# ospy_hw3_3.net
KiCad netlist of a schematic drawn in EAGLE
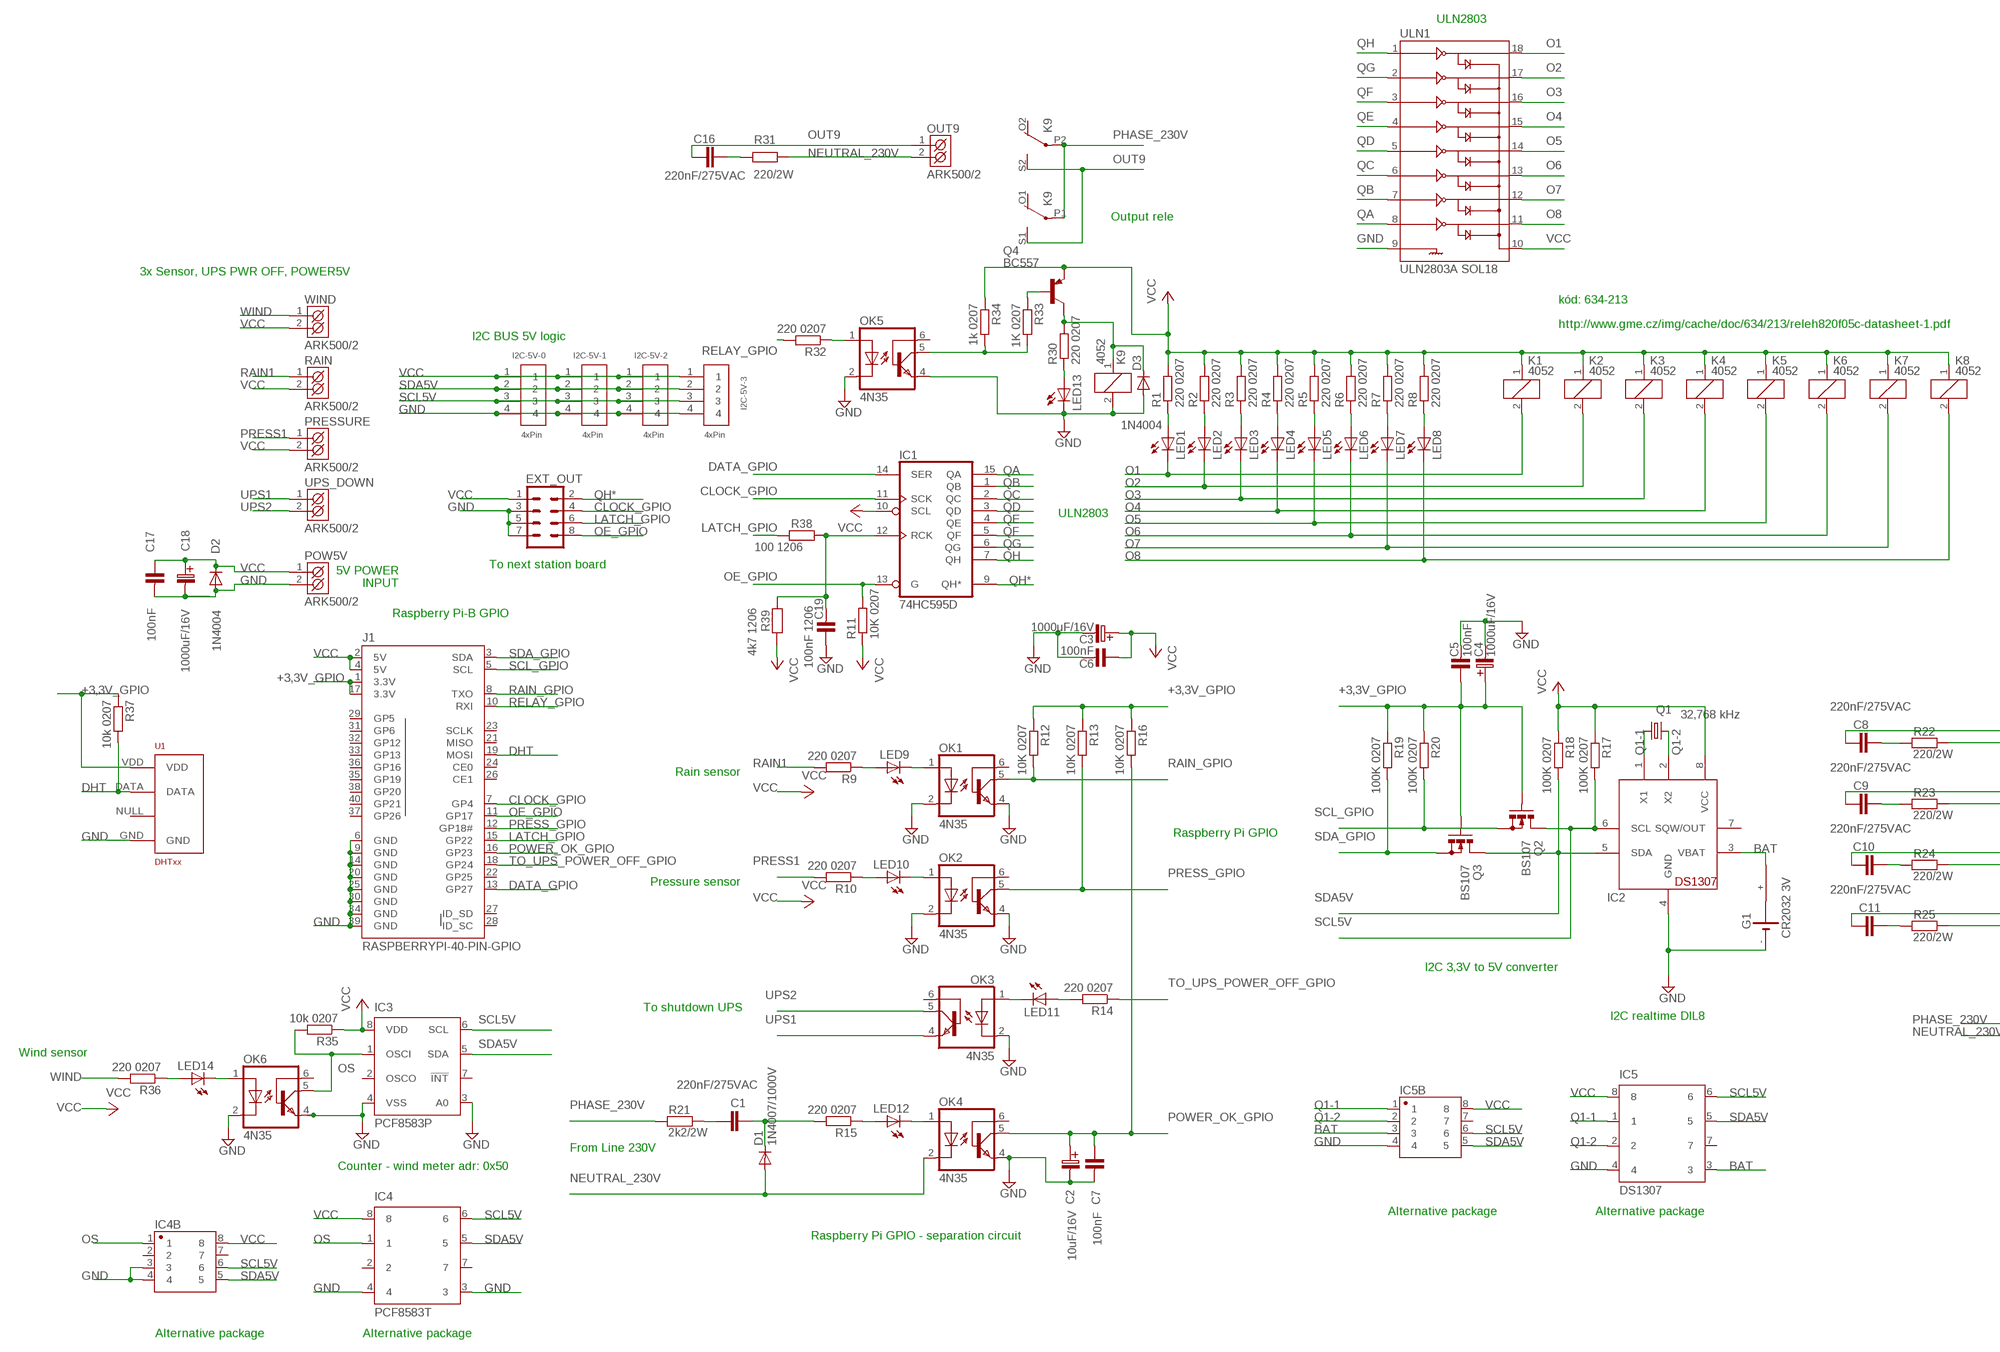
[diagram p0: schematic, sheet 1, part 1 of 2]
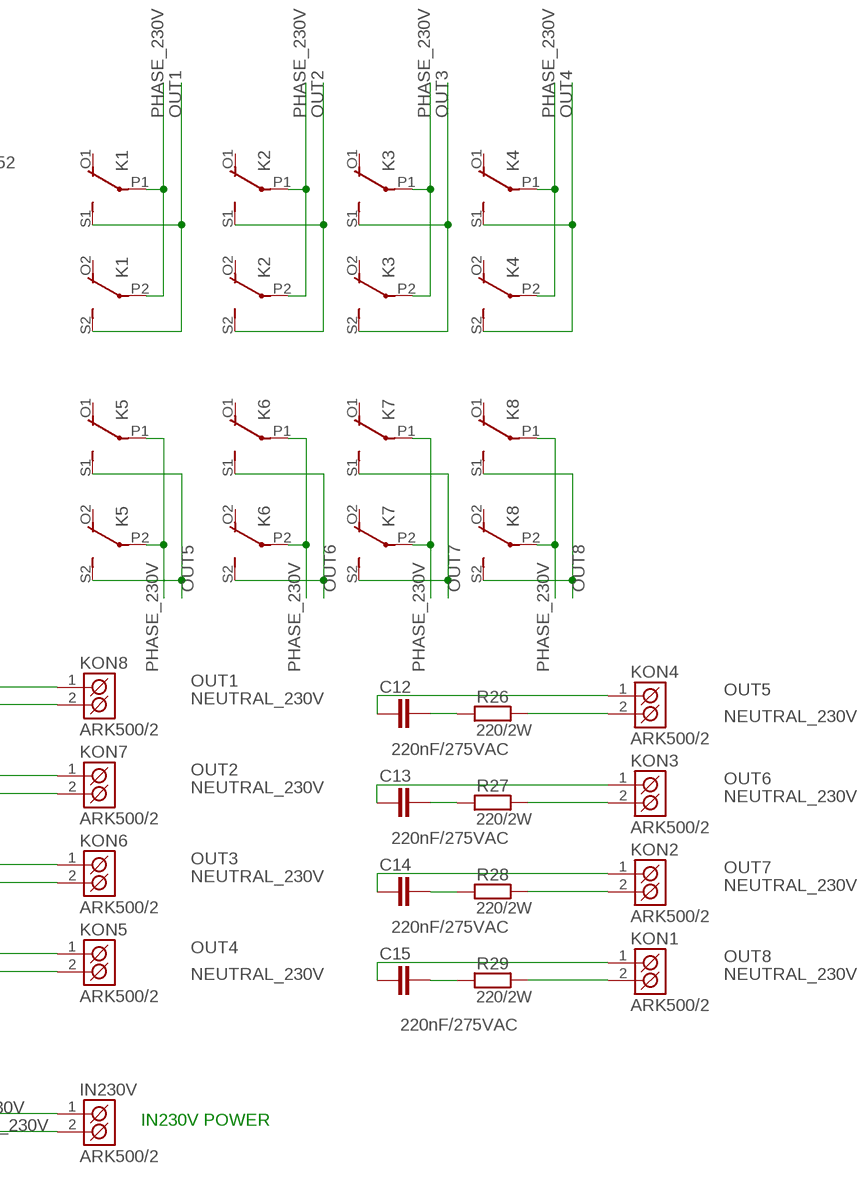
[diagram p1: schematic, sheet 1, part 2 of 2]

(export (version "E")
  (design (tool "Eeschema 10.0.6"))
  (components
    (comp (ref "C1")
      (value "220nF/275VAC")
      (footprint "eagle-import:C225-087X268")
      (libsource (lib "eagle-import") (part "C-EU225-087X268"))
    )
    (comp (ref "C2")
      (value "10uF/16V")
      (footprint "eagle-import:C_EL_5")
      (libsource (lib "eagle-import") (part "#_RADIAL_POUZDRA5"))
    )
    (comp (ref "C3")
      (value "1000uF/16V")
      (footprint "eagle-import:C_EL_5")
      (libsource (lib "eagle-import") (part "#_RADIAL_POUZDRA5"))
    )
    (comp (ref "C4")
      (value "1000uF/16V")
      (footprint "eagle-import:C_EL_5")
      (libsource (lib "eagle-import") (part "#_RADIAL_POUZDRA5"))
    )
    (comp (ref "C5")
      (value "100nF")
      (footprint "eagle-import:RM5_2,5")
      (libsource (lib "eagle-import") (part "100N-J/63V"))
    )
    (comp (ref "C6")
      (value "100nF")
      (footprint "eagle-import:RM5_2,5")
      (libsource (lib "eagle-import") (part "100N-J/63V"))
    )
    (comp (ref "C7")
      (value "100nF")
      (footprint "eagle-import:RM5_2,5")
      (libsource (lib "eagle-import") (part "100N-J/63V"))
    )
    (comp (ref "C8")
      (value "220nF/275VAC")
      (footprint "eagle-import:C225-087X268")
      (libsource (lib "eagle-import") (part "C-EU225-087X268"))
    )
    (comp (ref "C9")
      (value "220nF/275VAC")
      (footprint "eagle-import:C225-087X268")
      (libsource (lib "eagle-import") (part "C-EU225-087X268"))
    )
    (comp (ref "C10")
      (value "220nF/275VAC")
      (footprint "eagle-import:C225-087X268")
      (libsource (lib "eagle-import") (part "C-EU225-087X268"))
    )
    (comp (ref "C11")
      (value "220nF/275VAC")
      (footprint "eagle-import:C225-087X268")
      (libsource (lib "eagle-import") (part "C-EU225-087X268"))
    )
    (comp (ref "C12")
      (value "220nF/275VAC")
      (footprint "eagle-import:C225-087X268")
      (libsource (lib "eagle-import") (part "C-EU225-087X268"))
    )
    (comp (ref "C13")
      (value "220nF/275VAC")
      (footprint "eagle-import:C225-087X268")
      (libsource (lib "eagle-import") (part "C-EU225-087X268"))
    )
    (comp (ref "C14")
      (value "220nF/275VAC")
      (footprint "eagle-import:C225-087X268")
      (libsource (lib "eagle-import") (part "C-EU225-087X268"))
    )
    (comp (ref "C15")
      (value "220nF/275VAC")
      (footprint "eagle-import:C225-087X268")
      (libsource (lib "eagle-import") (part "C-EU225-087X268"))
    )
    (comp (ref "C16")
      (value "220nF/275VAC")
      (footprint "eagle-import:C225-087X268")
      (libsource (lib "eagle-import") (part "C-EU225-087X268"))
    )
    (comp (ref "C17")
      (value "100nF")
      (footprint "eagle-import:RM5_2,5")
      (libsource (lib "eagle-import") (part "100N-J/63V"))
    )
    (comp (ref "C18")
      (value "1000uF/16V")
      (footprint "eagle-import:C_EL_5")
      (libsource (lib "eagle-import") (part "#_RADIAL_POUZDRA5"))
    )
    (comp (ref "C19")
      (value "100nF 1206")
      (footprint "eagle-import:1206")
      (libsource (lib "eagle-import") (part "C-KER_1206"))
    )
    (comp (ref "D1")
      (value "1N4007/1000V")
      (footprint "eagle-import:DO41-10")
      (libsource (lib "eagle-import") (part "diode_1N4004"))
    )
    (comp (ref "D2")
      (value "1N4004")
      (footprint "eagle-import:DO41-10")
      (libsource (lib "eagle-import") (part "1N4004"))
    )
    (comp (ref "D3")
      (value "1N4004")
      (footprint "eagle-import:DO41-10")
      (libsource (lib "eagle-import") (part "1N4004"))
    )
    (comp (ref "EXT_OUT")
      (value "M04X2")
      (footprint "eagle-import:2X4")
      (libsource (lib "eagle-import") (part "M04X2"))
    )
    (comp (ref "G1")
      (value "CR2032 3V")
      (footprint "eagle-import:B2430UNI")
      (libsource (lib "eagle-import") (part "B2430UNI"))
    )
    (comp (ref "I2C-5V-0")
      (value "4xPin")
      (footprint "eagle-import:1X04-CLEANBIG")
      (libsource (lib "eagle-import") (part "1X4-CLEANBIG"))
    )
    (comp (ref "I2C-5V-1")
      (value "4xPin")
      (footprint "eagle-import:1X04-CLEANBIG")
      (libsource (lib "eagle-import") (part "1X4-CLEANBIG"))
    )
    (comp (ref "I2C-5V-2")
      (value "4xPin")
      (footprint "eagle-import:1X04-CLEANBIG")
      (libsource (lib "eagle-import") (part "1X4-CLEANBIG"))
    )
    (comp (ref "I2C-5V-3")
      (value "4xPin")
      (footprint "eagle-import:1X04-CLEANBIG")
      (libsource (lib "eagle-import") (part "1X4-CLEANBIG"))
    )
    (comp (ref "IC1")
      (value "74HC595D")
      (footprint "eagle-import:SO16")
      (libsource (lib "eagle-import") (part "74595DHC"))
    )
    (comp (ref "IC2")
      (value "DS1307")
      (footprint "eagle-import:DIL08")
      (libsource (lib "eagle-import") (part "DS1307"))
    )
    (comp (ref "IC3")
      (value "PCF8583P")
      (footprint "eagle-import:DIL08")
      (libsource (lib "eagle-import") (part "ds1307_pcf8583_PCF8583P"))
    )
    (comp (ref "IC4")
      (value "PCF8583T")
      (footprint "eagle-import:SO8-7_5")
      (libsource (lib "eagle-import") (part "PCF8583T"))
    )
    (comp (ref "IC4B")
      (value "GENERIC-SOIC8")
      (footprint "eagle-import:SO08-UNIVERSAL")
      (libsource (lib "eagle-import") (part "GENERIC-SOIC8"))
    )
    (comp (ref "IC5")
      (value "DS1307")
      (footprint "eagle-import:SO8-7_5")
      (libsource (lib "eagle-import") (part "PCF8583T"))
    )
    (comp (ref "IC5B")
      (value "GENERIC-SOIC8")
      (footprint "eagle-import:SO08-UNIVERSAL")
      (libsource (lib "eagle-import") (part "GENERIC-SOIC8"))
    )
    (comp (ref "IN230V")
      (value "ARK500/2")
      (footprint "eagle-import:ARK500_2")
      (libsource (lib "eagle-import") (part "ARK500/2"))
    )
    (comp (ref "J1")
      (value "RASPBERRYPI-40-PIN-GPIO")
      (footprint "eagle-import:2X20-SHROUDED")
      (libsource (lib "eagle-import") (part "RASPBERRYPI-40-PIN-GPIO"))
    )
    (comp (ref "K1")
      (value "4052")
      (footprint "eagle-import:F4052")
      (libsource (lib "eagle-import") (part "4052"))
    )
    (comp (ref "K2")
      (value "4052")
      (footprint "eagle-import:F4052")
      (libsource (lib "eagle-import") (part "4052"))
    )
    (comp (ref "K3")
      (value "4052")
      (footprint "eagle-import:F4052")
      (libsource (lib "eagle-import") (part "4052"))
    )
    (comp (ref "K4")
      (value "4052")
      (footprint "eagle-import:F4052")
      (libsource (lib "eagle-import") (part "4052"))
    )
    (comp (ref "K5")
      (value "4052")
      (footprint "eagle-import:F4052")
      (libsource (lib "eagle-import") (part "4052"))
    )
    (comp (ref "K6")
      (value "4052")
      (footprint "eagle-import:F4052")
      (libsource (lib "eagle-import") (part "4052"))
    )
    (comp (ref "K7")
      (value "4052")
      (footprint "eagle-import:F4052")
      (libsource (lib "eagle-import") (part "4052"))
    )
    (comp (ref "K8")
      (value "4052")
      (footprint "eagle-import:F4052")
      (libsource (lib "eagle-import") (part "4052"))
    )
    (comp (ref "K9")
      (value "4052")
      (footprint "eagle-import:F4052")
      (libsource (lib "eagle-import") (part "4052"))
    )
    (comp (ref "KON1")
      (value "ARK500/2")
      (footprint "eagle-import:ARK500_2")
      (libsource (lib "eagle-import") (part "ARK500/2"))
    )
    (comp (ref "KON2")
      (value "ARK500/2")
      (footprint "eagle-import:ARK500_2")
      (libsource (lib "eagle-import") (part "ARK500/2"))
    )
    (comp (ref "KON3")
      (value "ARK500/2")
      (footprint "eagle-import:ARK500_2")
      (libsource (lib "eagle-import") (part "ARK500/2"))
    )
    (comp (ref "KON4")
      (value "ARK500/2")
      (footprint "eagle-import:ARK500_2")
      (libsource (lib "eagle-import") (part "ARK500/2"))
    )
    (comp (ref "KON5")
      (value "ARK500/2")
      (footprint "eagle-import:ARK500_2")
      (libsource (lib "eagle-import") (part "ARK500/2"))
    )
    (comp (ref "KON6")
      (value "ARK500/2")
      (footprint "eagle-import:ARK500_2")
      (libsource (lib "eagle-import") (part "ARK500/2"))
    )
    (comp (ref "KON7")
      (value "ARK500/2")
      (footprint "eagle-import:ARK500_2")
      (libsource (lib "eagle-import") (part "ARK500/2"))
    )
    (comp (ref "KON8")
      (value "ARK500/2")
      (footprint "eagle-import:ARK500_2")
      (libsource (lib "eagle-import") (part "ARK500/2"))
    )
    (comp (ref "LED1")
      (value "LED3MM")
      (footprint "eagle-import:LED3MM")
      (libsource (lib "eagle-import") (part "LED3MM"))
    )
    (comp (ref "LED2")
      (value "LED3MM")
      (footprint "eagle-import:LED3MM")
      (libsource (lib "eagle-import") (part "LED3MM"))
    )
    (comp (ref "LED3")
      (value "LED3MM")
      (footprint "eagle-import:LED3MM")
      (libsource (lib "eagle-import") (part "LED3MM"))
    )
    (comp (ref "LED4")
      (value "LED3MM")
      (footprint "eagle-import:LED3MM")
      (libsource (lib "eagle-import") (part "LED3MM"))
    )
    (comp (ref "LED5")
      (value "LED3MM")
      (footprint "eagle-import:LED3MM")
      (libsource (lib "eagle-import") (part "LED3MM"))
    )
    (comp (ref "LED6")
      (value "LED3MM")
      (footprint "eagle-import:LED3MM")
      (libsource (lib "eagle-import") (part "LED3MM"))
    )
    (comp (ref "LED7")
      (value "LED3MM")
      (footprint "eagle-import:LED3MM")
      (libsource (lib "eagle-import") (part "LED3MM"))
    )
    (comp (ref "LED8")
      (value "LED3MM")
      (footprint "eagle-import:LED3MM")
      (libsource (lib "eagle-import") (part "LED3MM"))
    )
    (comp (ref "LED9")
      (value "LED3MM")
      (footprint "eagle-import:LED3MM")
      (libsource (lib "eagle-import") (part "LED3MM"))
    )
    (comp (ref "LED10")
      (value "LED3MM")
      (footprint "eagle-import:LED3MM")
      (libsource (lib "eagle-import") (part "LED3MM"))
    )
    (comp (ref "LED11")
      (value "LED3MM")
      (footprint "eagle-import:LED3MM")
      (libsource (lib "eagle-import") (part "LED3MM"))
    )
    (comp (ref "LED12")
      (value "LED3MM")
      (footprint "eagle-import:LED3MM")
      (libsource (lib "eagle-import") (part "LED3MM"))
    )
    (comp (ref "LED13")
      (value "LED3MM")
      (footprint "eagle-import:LED3MM")
      (libsource (lib "eagle-import") (part "LED3MM"))
    )
    (comp (ref "LED14")
      (value "LED3MM")
      (footprint "eagle-import:LED3MM")
      (libsource (lib "eagle-import") (part "LED3MM"))
    )
    (comp (ref "OK1")
      (value "4N35")
      (footprint "eagle-import:DIL06")
      (fields (field (name "MF") "FAIRCHILD SEMICONDUCTOR"))
      (libsource (lib "eagle-import") (part "4N35"))
    )
    (comp (ref "OK2")
      (value "4N35")
      (footprint "eagle-import:DIL06")
      (fields (field (name "MF") "FAIRCHILD SEMICONDUCTOR"))
      (libsource (lib "eagle-import") (part "4N35"))
    )
    (comp (ref "OK3")
      (value "4N35")
      (footprint "eagle-import:DIL06")
      (fields (field (name "MF") "FAIRCHILD SEMICONDUCTOR"))
      (libsource (lib "eagle-import") (part "4N35"))
    )
    (comp (ref "OK4")
      (value "4N35")
      (footprint "eagle-import:DIL06")
      (fields (field (name "MF") "FAIRCHILD SEMICONDUCTOR"))
      (libsource (lib "eagle-import") (part "4N35"))
    )
    (comp (ref "OK5")
      (value "4N35")
      (footprint "eagle-import:DIL06")
      (fields (field (name "MF") "FAIRCHILD SEMICONDUCTOR"))
      (libsource (lib "eagle-import") (part "4N35"))
    )
    (comp (ref "OK6")
      (value "4N35")
      (footprint "eagle-import:DIL06")
      (fields (field (name "MF") "FAIRCHILD SEMICONDUCTOR"))
      (libsource (lib "eagle-import") (part "4N35"))
    )
    (comp (ref "OUT9")
      (value "ARK500/2")
      (footprint "eagle-import:ARK500_2")
      (libsource (lib "eagle-import") (part "ARK500/2"))
    )
    (comp (ref "POW5V")
      (value "ARK500/2")
      (footprint "eagle-import:ARK500_2")
      (libsource (lib "eagle-import") (part "ARK500/2"))
    )
    (comp (ref "PRESSURE")
      (value "ARK500/2")
      (footprint "eagle-import:ARK500_2")
      (libsource (lib "eagle-import") (part "ARK500/2"))
    )
    (comp (ref "Q1")
      (value "32,768 kHz")
      (footprint "eagle-import:TC26V")
      (libsource (lib "eagle-import") (part "CRYSTALTC26V"))
    )
    (comp (ref "Q2")
      (value "BS107")
      (footprint "eagle-import:SOT54E")
      (libsource (lib "eagle-import") (part "BS170"))
    )
    (comp (ref "Q3")
      (value "BS107")
      (footprint "eagle-import:SOT54E")
      (libsource (lib "eagle-import") (part "BS170"))
    )
    (comp (ref "Q4")
      (value "BC557")
      (footprint "eagle-import:TO92")
      (libsource (lib "eagle-import") (part "BC557"))
    )
    (comp (ref "R1")
      (value "220 0207")
      (footprint "eagle-import:0207_10")
      (libsource (lib "eagle-import") (part "R-EU_0207/10"))
    )
    (comp (ref "R2")
      (value "220 0207")
      (footprint "eagle-import:0207_10")
      (libsource (lib "eagle-import") (part "R-EU_0207/10"))
    )
    (comp (ref "R3")
      (value "220 0207")
      (footprint "eagle-import:0207_10")
      (libsource (lib "eagle-import") (part "R-EU_0207/10"))
    )
    (comp (ref "R4")
      (value "220 0207")
      (footprint "eagle-import:0207_10")
      (libsource (lib "eagle-import") (part "R-EU_0207/10"))
    )
    (comp (ref "R5")
      (value "220 0207")
      (footprint "eagle-import:0207_10")
      (libsource (lib "eagle-import") (part "R-EU_0207/10"))
    )
    (comp (ref "R6")
      (value "220 0207")
      (footprint "eagle-import:0207_10")
      (libsource (lib "eagle-import") (part "R-EU_0207/10"))
    )
    (comp (ref "R7")
      (value "220 0207")
      (footprint "eagle-import:0207_10")
      (libsource (lib "eagle-import") (part "R-EU_0207/10"))
    )
    (comp (ref "R8")
      (value "220 0207")
      (footprint "eagle-import:0207_10")
      (libsource (lib "eagle-import") (part "R-EU_0207/10"))
    )
    (comp (ref "R9")
      (value "220 0207")
      (footprint "eagle-import:0207_10")
      (libsource (lib "eagle-import") (part "R-EU_0207/10"))
    )
    (comp (ref "R10")
      (value "220 0207")
      (footprint "eagle-import:0207_10")
      (libsource (lib "eagle-import") (part "R-EU_0207/10"))
    )
    (comp (ref "R11")
      (value "10K 0207")
      (footprint "eagle-import:0207_10")
      (libsource (lib "eagle-import") (part "R-EU_0207/10"))
    )
    (comp (ref "R12")
      (value "10K 0207")
      (footprint "eagle-import:0207_10")
      (libsource (lib "eagle-import") (part "R-EU_0207/10"))
    )
    (comp (ref "R13")
      (value "10K 0207")
      (footprint "eagle-import:0207_10")
      (libsource (lib "eagle-import") (part "R-EU_0207/10"))
    )
    (comp (ref "R14")
      (value "220 0207")
      (footprint "eagle-import:0207_10")
      (libsource (lib "eagle-import") (part "R-EU_0207/10"))
    )
    (comp (ref "R15")
      (value "220 0207")
      (footprint "eagle-import:0207_10")
      (libsource (lib "eagle-import") (part "R-EU_0207/10"))
    )
    (comp (ref "R16")
      (value "10K 0207")
      (footprint "eagle-import:0207_10")
      (libsource (lib "eagle-import") (part "R-EU_0207/10"))
    )
    (comp (ref "R17")
      (value "100K 0207")
      (footprint "eagle-import:0207_10")
      (libsource (lib "eagle-import") (part "R-EU_0207/10"))
    )
    (comp (ref "R18")
      (value "100K 0207")
      (footprint "eagle-import:0207_10")
      (libsource (lib "eagle-import") (part "R-EU_0207/10"))
    )
    (comp (ref "R19")
      (value "100K 0207")
      (footprint "eagle-import:0207_10")
      (libsource (lib "eagle-import") (part "R-EU_0207/10"))
    )
    (comp (ref "R20")
      (value "100K 0207")
      (footprint "eagle-import:0207_10")
      (libsource (lib "eagle-import") (part "R-EU_0207/10"))
    )
    (comp (ref "R21")
      (value "2k2/2W")
      (footprint "eagle-import:R__2W")
      (libsource (lib "eagle-import") (part "W2_220R"))
    )
    (comp (ref "R22")
      (value "220/2W")
      (footprint "eagle-import:R__2W")
      (libsource (lib "eagle-import") (part "W2_220R"))
    )
    (comp (ref "R23")
      (value "220/2W")
      (footprint "eagle-import:R__2W")
      (libsource (lib "eagle-import") (part "W2_220R"))
    )
    (comp (ref "R24")
      (value "220/2W")
      (footprint "eagle-import:R__2W")
      (libsource (lib "eagle-import") (part "W2_220R"))
    )
    (comp (ref "R25")
      (value "220/2W")
      (footprint "eagle-import:R__2W")
      (libsource (lib "eagle-import") (part "W2_220R"))
    )
    (comp (ref "R26")
      (value "220/2W")
      (footprint "eagle-import:R__2W")
      (libsource (lib "eagle-import") (part "W2_220R"))
    )
    (comp (ref "R27")
      (value "220/2W")
      (footprint "eagle-import:R__2W")
      (libsource (lib "eagle-import") (part "W2_220R"))
    )
    (comp (ref "R28")
      (value "220/2W")
      (footprint "eagle-import:R__2W")
      (libsource (lib "eagle-import") (part "W2_220R"))
    )
    (comp (ref "R29")
      (value "220/2W")
      (footprint "eagle-import:R__2W")
      (libsource (lib "eagle-import") (part "W2_220R"))
    )
    (comp (ref "R30")
      (value "220 0207")
      (footprint "eagle-import:0207_10")
      (libsource (lib "eagle-import") (part "R-EU_0207/10"))
    )
    (comp (ref "R31")
      (value "220/2W")
      (footprint "eagle-import:R__2W")
      (libsource (lib "eagle-import") (part "W2_220R"))
    )
    (comp (ref "R32")
      (value "220 0207")
      (footprint "eagle-import:0207_10")
      (libsource (lib "eagle-import") (part "R-EU_0207/10"))
    )
    (comp (ref "R33")
      (value "1K 0207")
      (footprint "eagle-import:0207_10")
      (libsource (lib "eagle-import") (part "R-EU_0207/10"))
    )
    (comp (ref "R34")
      (value "1k 0207")
      (footprint "eagle-import:0207_10")
      (libsource (lib "eagle-import") (part "R-EU_0207/10"))
    )
    (comp (ref "R35")
      (value "10k 0207")
      (footprint "eagle-import:0207_10")
      (libsource (lib "eagle-import") (part "R-EU_0207/10"))
    )
    (comp (ref "R36")
      (value "220 0207")
      (footprint "eagle-import:0207_10")
      (libsource (lib "eagle-import") (part "R-EU_0207/10"))
    )
    (comp (ref "R37")
      (value "10k 0207")
      (footprint "eagle-import:0207_10")
      (libsource (lib "eagle-import") (part "R-EU_0207/10"))
    )
    (comp (ref "R38")
      (value "100 1206")
      (footprint "eagle-import:1206")
      (libsource (lib "eagle-import") (part "R_1206"))
    )
    (comp (ref "R39")
      (value "4k7 1206")
      (footprint "eagle-import:1206")
      (libsource (lib "eagle-import") (part "R_1206"))
    )
    (comp (ref "RAIN")
      (value "ARK500/2")
      (footprint "eagle-import:ARK500_2")
      (libsource (lib "eagle-import") (part "ARK500/2"))
    )
    (comp (ref "U1")
      (value "DHTxx")
      (footprint "eagle-import:RHT03_DHT-22_RA")
      (libsource (lib "eagle-import") (part "RHT03_DHT-22_AM2302RA"))
    )
    (comp (ref "ULN1")
      (value "ULN2803A SOL18")
      (footprint "eagle-import:SO18L")
      (libsource (lib "eagle-import") (part "ULN2803SOICW"))
    )
    (comp (ref "UPS_DOWN")
      (value "ARK500/2")
      (footprint "eagle-import:ARK500_2")
      (libsource (lib "eagle-import") (part "ARK500/2"))
    )
    (comp (ref "WIND")
      (value "ARK500/2")
      (footprint "eagle-import:ARK500_2")
      (libsource (lib "eagle-import") (part "ARK500/2"))
    )
  )
  (nets
    (net (code "1") (name "/+3,3V_GPIO") (class "Default")
      (node (ref "C4") (pin "C+") (pinfunction "C_EL+_C+") (pintype "passive"))
      (node (ref "C5") (pin "1") (pinfunction "1_1") (pintype "passive"))
      (node (ref "J1") (pin "1") (pinfunction "3.3V_1") (pintype "power_in"))
      (node (ref "J1") (pin "17") (pinfunction "3.3V_17") (pintype "power_in"))
      (node (ref "Q2") (pin "G") (pinfunction "G_G") (pintype "passive"))
      (node (ref "Q3") (pin "G") (pinfunction "G_G") (pintype "passive"))
      (node (ref "R12") (pin "1") (pinfunction "1_1") (pintype "passive"))
      (node (ref "R13") (pin "1") (pinfunction "1_1") (pintype "passive"))
      (node (ref "R16") (pin "1") (pinfunction "1_1") (pintype "passive"))
      (node (ref "R19") (pin "1") (pinfunction "1_1") (pintype "passive"))
      (node (ref "R20") (pin "1") (pinfunction "1_1") (pintype "passive"))
      (node (ref "R37") (pin "1") (pinfunction "1_1") (pintype "passive"))
      (node (ref "U1") (pin "VDD") (pinfunction "VDD_VDD") (pintype "power_in"))
    )
    (net (code "2") (name "/BAT") (class "Default")
      (node (ref "G1") (pin "+") (pinfunction "+_+") (pintype "passive"))
      (node (ref "IC2") (pin "3") (pinfunction "VBAT_3") (pintype "power_in"))
      (node (ref "IC5") (pin "3") (pinfunction "3_3") (pintype "input"))
      (node (ref "IC5B") (pin "3") (pinfunction "3_3") (pintype "bidirectional"))
    )
    (net (code "3") (name "/CLOCK_GPIO") (class "Default")
      (node (ref "EXT_OUT") (pin "4") (pinfunction "4_4") (pintype "passive"))
      (node (ref "IC1") (pin "11") (pinfunction "SCK_11") (pintype "input"))
      (node (ref "J1") (pin "7") (pinfunction "GP4_7") (pintype "bidirectional"))
    )
    (net (code "4") (name "/DATA_GPIO") (class "Default")
      (node (ref "IC1") (pin "14") (pinfunction "SER_14") (pintype "input"))
      (node (ref "J1") (pin "13") (pinfunction "GP27_13") (pintype "bidirectional"))
    )
    (net (code "5") (name "/DHT") (class "Default")
      (node (ref "J1") (pin "19") (pinfunction "MOSI_19") (pintype "output"))
      (node (ref "R37") (pin "2") (pinfunction "2_2") (pintype "passive"))
      (node (ref "U1") (pin "DATA") (pinfunction "DATA_DATA") (pintype "bidirectional"))
    )
    (net (code "6") (name "/LATCH_GPIO") (class "Default")
      (node (ref "EXT_OUT") (pin "6") (pinfunction "6_6") (pintype "passive"))
      (node (ref "J1") (pin "15") (pinfunction "GP22_15") (pintype "bidirectional"))
      (node (ref "R38") (pin "1") (pinfunction "1_1") (pintype "passive"))
    )
    (net (code "7") (name "/NEUTRAL_230V") (class "Default")
      (node (ref "D1") (pin "A") (pinfunction "A_A") (pintype "passive"))
      (node (ref "IN230V") (pin "2") (pinfunction "K2_2") (pintype "passive"))
      (node (ref "KON1") (pin "2") (pinfunction "K2_2") (pintype "passive"))
      (node (ref "KON2") (pin "2") (pinfunction "K2_2") (pintype "passive"))
      (node (ref "KON3") (pin "2") (pinfunction "K2_2") (pintype "passive"))
      (node (ref "KON4") (pin "2") (pinfunction "K2_2") (pintype "passive"))
      (node (ref "KON5") (pin "2") (pinfunction "K2_2") (pintype "passive"))
      (node (ref "KON6") (pin "2") (pinfunction "K2_2") (pintype "passive"))
      (node (ref "KON7") (pin "2") (pinfunction "K2_2") (pintype "passive"))
      (node (ref "KON8") (pin "2") (pinfunction "K2_2") (pintype "passive"))
      (node (ref "OK4") (pin "2") (pinfunction "C_2") (pintype "passive"))
      (node (ref "OUT9") (pin "2") (pinfunction "K2_2") (pintype "passive"))
      (node (ref "R22") (pin "2") (pinfunction "2_2") (pintype "passive"))
      (node (ref "R23") (pin "2") (pinfunction "2_2") (pintype "passive"))
      (node (ref "R24") (pin "2") (pinfunction "2_2") (pintype "passive"))
      (node (ref "R25") (pin "2") (pinfunction "2_2") (pintype "passive"))
      (node (ref "R26") (pin "2") (pinfunction "2_2") (pintype "passive"))
      (node (ref "R27") (pin "2") (pinfunction "2_2") (pintype "passive"))
      (node (ref "R28") (pin "2") (pinfunction "2_2") (pintype "passive"))
      (node (ref "R29") (pin "2") (pinfunction "2_2") (pintype "passive"))
      (node (ref "R31") (pin "2") (pinfunction "2_2") (pintype "passive"))
    )
    (net (code "8") (name "/O1") (class "Default")
      (node (ref "K1") (pin "2") (pinfunction "2_2") (pintype "passive"))
      (node (ref "LED1") (pin "K") (pinfunction "C_K") (pintype "passive"))
      (node (ref "ULN1") (pin "18") (pinfunction "18_18") (pintype "bidirectional"))
    )
    (net (code "9") (name "/O2") (class "Default")
      (node (ref "K2") (pin "2") (pinfunction "2_2") (pintype "passive"))
      (node (ref "LED2") (pin "K") (pinfunction "C_K") (pintype "passive"))
      (node (ref "ULN1") (pin "17") (pinfunction "17_17") (pintype "bidirectional"))
    )
    (net (code "10") (name "/O3") (class "Default")
      (node (ref "K3") (pin "2") (pinfunction "2_2") (pintype "passive"))
      (node (ref "LED3") (pin "K") (pinfunction "C_K") (pintype "passive"))
      (node (ref "ULN1") (pin "16") (pinfunction "16_16") (pintype "bidirectional"))
    )
    (net (code "11") (name "/O4") (class "Default")
      (node (ref "K4") (pin "2") (pinfunction "2_2") (pintype "passive"))
      (node (ref "LED4") (pin "K") (pinfunction "C_K") (pintype "passive"))
      (node (ref "ULN1") (pin "15") (pinfunction "15_15") (pintype "bidirectional"))
    )
    (net (code "12") (name "/O5") (class "Default")
      (node (ref "K5") (pin "2") (pinfunction "2_2") (pintype "passive"))
      (node (ref "LED5") (pin "K") (pinfunction "C_K") (pintype "passive"))
      (node (ref "ULN1") (pin "14") (pinfunction "14_14") (pintype "bidirectional"))
    )
    (net (code "13") (name "/O6") (class "Default")
      (node (ref "K6") (pin "2") (pinfunction "2_2") (pintype "passive"))
      (node (ref "LED6") (pin "K") (pinfunction "C_K") (pintype "passive"))
      (node (ref "ULN1") (pin "13") (pinfunction "13_13") (pintype "bidirectional"))
    )
    (net (code "14") (name "/O7") (class "Default")
      (node (ref "K7") (pin "2") (pinfunction "2_2") (pintype "passive"))
      (node (ref "LED7") (pin "K") (pinfunction "C_K") (pintype "passive"))
      (node (ref "ULN1") (pin "12") (pinfunction "12_12") (pintype "bidirectional"))
    )
    (net (code "15") (name "/O8") (class "Default")
      (node (ref "K8") (pin "2") (pinfunction "2_2") (pintype "passive"))
      (node (ref "LED8") (pin "K") (pinfunction "C_K") (pintype "passive"))
      (node (ref "ULN1") (pin "11") (pinfunction "11_11") (pintype "bidirectional"))
    )
    (net (code "16") (name "/OE_GPIO") (class "Default")
      (node (ref "EXT_OUT") (pin "8") (pinfunction "8_8") (pintype "passive"))
      (node (ref "IC1") (pin "13") (pinfunction "G_13") (pintype "input"))
      (node (ref "J1") (pin "11") (pinfunction "GP17_11") (pintype "bidirectional"))
      (node (ref "R11") (pin "2") (pinfunction "2_2") (pintype "passive"))
    )
    (net (code "17") (name "/OS") (class "Default")
      (node (ref "IC3") (pin "1") (pinfunction "OSCI_1") (pintype "input"))
      (node (ref "IC4") (pin "1") (pinfunction "1_1") (pintype "input"))
      (node (ref "IC4B") (pin "1") (pinfunction "1_1") (pintype "bidirectional"))
      (node (ref "OK6") (pin "5") (pinfunction "COL_5") (pintype "passive"))
      (node (ref "R35") (pin "2") (pinfunction "2_2") (pintype "passive"))
    )
    (net (code "18") (name "/OUT1") (class "Default")
      (node (ref "C8") (pin "1") (pinfunction "1_1") (pintype "passive"))
      (node (ref "K1") (pin "S1") (pinfunction "S_S1") (pintype "passive"))
      (node (ref "K1") (pin "S2") (pinfunction "S_S2") (pintype "passive"))
      (node (ref "KON8") (pin "1") (pinfunction "K1_1") (pintype "passive"))
    )
    (net (code "19") (name "/OUT2") (class "Default")
      (node (ref "C9") (pin "1") (pinfunction "1_1") (pintype "passive"))
      (node (ref "K2") (pin "S1") (pinfunction "S_S1") (pintype "passive"))
      (node (ref "K2") (pin "S2") (pinfunction "S_S2") (pintype "passive"))
      (node (ref "KON7") (pin "1") (pinfunction "K1_1") (pintype "passive"))
    )
    (net (code "20") (name "/OUT3") (class "Default")
      (node (ref "C10") (pin "1") (pinfunction "1_1") (pintype "passive"))
      (node (ref "K3") (pin "S1") (pinfunction "S_S1") (pintype "passive"))
      (node (ref "K3") (pin "S2") (pinfunction "S_S2") (pintype "passive"))
      (node (ref "KON6") (pin "1") (pinfunction "K1_1") (pintype "passive"))
    )
    (net (code "21") (name "/OUT4") (class "Default")
      (node (ref "C11") (pin "1") (pinfunction "1_1") (pintype "passive"))
      (node (ref "K4") (pin "S1") (pinfunction "S_S1") (pintype "passive"))
      (node (ref "K4") (pin "S2") (pinfunction "S_S2") (pintype "passive"))
      (node (ref "KON5") (pin "1") (pinfunction "K1_1") (pintype "passive"))
    )
    (net (code "22") (name "/OUT5") (class "Default")
      (node (ref "C12") (pin "1") (pinfunction "1_1") (pintype "passive"))
      (node (ref "K5") (pin "S1") (pinfunction "S_S1") (pintype "passive"))
      (node (ref "K5") (pin "S2") (pinfunction "S_S2") (pintype "passive"))
      (node (ref "KON4") (pin "1") (pinfunction "K1_1") (pintype "passive"))
    )
    (net (code "23") (name "/OUT6") (class "Default")
      (node (ref "C13") (pin "1") (pinfunction "1_1") (pintype "passive"))
      (node (ref "K6") (pin "S1") (pinfunction "S_S1") (pintype "passive"))
      (node (ref "K6") (pin "S2") (pinfunction "S_S2") (pintype "passive"))
      (node (ref "KON3") (pin "1") (pinfunction "K1_1") (pintype "passive"))
    )
    (net (code "24") (name "/OUT7") (class "Default")
      (node (ref "C14") (pin "1") (pinfunction "1_1") (pintype "passive"))
      (node (ref "K7") (pin "S1") (pinfunction "S_S1") (pintype "passive"))
      (node (ref "K7") (pin "S2") (pinfunction "S_S2") (pintype "passive"))
      (node (ref "KON2") (pin "1") (pinfunction "K1_1") (pintype "passive"))
    )
    (net (code "25") (name "/OUT8") (class "Default")
      (node (ref "C15") (pin "1") (pinfunction "1_1") (pintype "passive"))
      (node (ref "K8") (pin "S1") (pinfunction "S_S1") (pintype "passive"))
      (node (ref "K8") (pin "S2") (pinfunction "S_S2") (pintype "passive"))
      (node (ref "KON1") (pin "1") (pinfunction "K1_1") (pintype "passive"))
    )
    (net (code "26") (name "/OUT9") (class "Default")
      (node (ref "C16") (pin "1") (pinfunction "1_1") (pintype "passive"))
      (node (ref "K9") (pin "S1") (pinfunction "S_S1") (pintype "passive"))
      (node (ref "K9") (pin "S2") (pinfunction "S_S2") (pintype "passive"))
      (node (ref "OUT9") (pin "1") (pinfunction "K1_1") (pintype "passive"))
    )
    (net (code "27") (name "/PHASE_230V") (class "Default")
      (node (ref "IN230V") (pin "1") (pinfunction "K1_1") (pintype "passive"))
      (node (ref "K1") (pin "P1") (pinfunction "P_P1") (pintype "passive"))
      (node (ref "K1") (pin "P2") (pinfunction "P_P2") (pintype "passive"))
      (node (ref "K2") (pin "P1") (pinfunction "P_P1") (pintype "passive"))
      (node (ref "K2") (pin "P2") (pinfunction "P_P2") (pintype "passive"))
      (node (ref "K3") (pin "P1") (pinfunction "P_P1") (pintype "passive"))
      (node (ref "K3") (pin "P2") (pinfunction "P_P2") (pintype "passive"))
      (node (ref "K4") (pin "P1") (pinfunction "P_P1") (pintype "passive"))
      (node (ref "K4") (pin "P2") (pinfunction "P_P2") (pintype "passive"))
      (node (ref "K5") (pin "P1") (pinfunction "P_P1") (pintype "passive"))
      (node (ref "K5") (pin "P2") (pinfunction "P_P2") (pintype "passive"))
      (node (ref "K6") (pin "P1") (pinfunction "P_P1") (pintype "passive"))
      (node (ref "K6") (pin "P2") (pinfunction "P_P2") (pintype "passive"))
      (node (ref "K7") (pin "P1") (pinfunction "P_P1") (pintype "passive"))
      (node (ref "K7") (pin "P2") (pinfunction "P_P2") (pintype "passive"))
      (node (ref "K8") (pin "P1") (pinfunction "P_P1") (pintype "passive"))
      (node (ref "K8") (pin "P2") (pinfunction "P_P2") (pintype "passive"))
      (node (ref "K9") (pin "P1") (pinfunction "P_P1") (pintype "passive"))
      (node (ref "K9") (pin "P2") (pinfunction "P_P2") (pintype "passive"))
      (node (ref "R21") (pin "1") (pinfunction "1_1") (pintype "passive"))
    )
    (net (code "28") (name "/POWER_OK_GPIO") (class "Default")
      (node (ref "C2") (pin "C+") (pinfunction "C_EL+_C+") (pintype "passive"))
      (node (ref "C7") (pin "1") (pinfunction "1_1") (pintype "passive"))
      (node (ref "J1") (pin "16") (pinfunction "GP23_16") (pintype "bidirectional"))
      (node (ref "OK4") (pin "5") (pinfunction "COL_5") (pintype "passive"))
      (node (ref "R16") (pin "2") (pinfunction "2_2") (pintype "passive"))
    )
    (net (code "29") (name "/PRESS1") (class "Default")
      (node (ref "PRESSURE") (pin "1") (pinfunction "K1_1") (pintype "passive"))
      (node (ref "R10") (pin "2") (pinfunction "2_2") (pintype "passive"))
    )
    (net (code "30") (name "/PRESS_GPIO") (class "Default")
      (node (ref "J1") (pin "12") (pinfunction "GP18#_12") (pintype "bidirectional"))
      (node (ref "OK2") (pin "5") (pinfunction "COL_5") (pintype "passive"))
      (node (ref "R13") (pin "2") (pinfunction "2_2") (pintype "passive"))
    )
    (net (code "31") (name "/Q1-1") (class "Default")
      (node (ref "IC2") (pin "1") (pinfunction "X1_1") (pintype "passive"))
      (node (ref "IC5") (pin "1") (pinfunction "1_1") (pintype "input"))
      (node (ref "IC5B") (pin "1") (pinfunction "1_1") (pintype "bidirectional"))
      (node (ref "Q1") (pin "1") (pinfunction "1_1") (pintype "passive"))
    )
    (net (code "32") (name "/Q1-2") (class "Default")
      (node (ref "IC2") (pin "2") (pinfunction "X2_2") (pintype "passive"))
      (node (ref "IC5") (pin "2") (pinfunction "2_2") (pintype "output"))
      (node (ref "IC5B") (pin "2") (pinfunction "2_2") (pintype "bidirectional"))
      (node (ref "Q1") (pin "2") (pinfunction "2_2") (pintype "passive"))
    )
    (net (code "33") (name "/QA") (class "Default")
      (node (ref "IC1") (pin "15") (pinfunction "QA_15") (pintype "tri_state"))
      (node (ref "ULN1") (pin "8") (pinfunction "8_8") (pintype "bidirectional"))
    )
    (net (code "34") (name "/QB") (class "Default")
      (node (ref "IC1") (pin "1") (pinfunction "QB_1") (pintype "tri_state"))
      (node (ref "ULN1") (pin "7") (pinfunction "7_7") (pintype "bidirectional"))
    )
    (net (code "35") (name "/QC") (class "Default")
      (node (ref "IC1") (pin "2") (pinfunction "QC_2") (pintype "tri_state"))
      (node (ref "ULN1") (pin "6") (pinfunction "6_6") (pintype "bidirectional"))
    )
    (net (code "36") (name "/QD") (class "Default")
      (node (ref "IC1") (pin "3") (pinfunction "QD_3") (pintype "tri_state"))
      (node (ref "ULN1") (pin "5") (pinfunction "5_5") (pintype "bidirectional"))
    )
    (net (code "37") (name "/QE") (class "Default")
      (node (ref "IC1") (pin "4") (pinfunction "QE_4") (pintype "tri_state"))
      (node (ref "ULN1") (pin "4") (pinfunction "4_4") (pintype "bidirectional"))
    )
    (net (code "38") (name "/QF") (class "Default")
      (node (ref "IC1") (pin "5") (pinfunction "QF_5") (pintype "tri_state"))
      (node (ref "ULN1") (pin "3") (pinfunction "3_3") (pintype "bidirectional"))
    )
    (net (code "39") (name "/QG") (class "Default")
      (node (ref "IC1") (pin "6") (pinfunction "QG_6") (pintype "tri_state"))
      (node (ref "ULN1") (pin "2") (pinfunction "2_2") (pintype "bidirectional"))
    )
    (net (code "40") (name "/QH") (class "Default")
      (node (ref "IC1") (pin "7") (pinfunction "QH_7") (pintype "tri_state"))
      (node (ref "ULN1") (pin "1") (pinfunction "1_1") (pintype "bidirectional"))
    )
    (net (code "41") (name "/QH*") (class "Default")
      (node (ref "EXT_OUT") (pin "2") (pinfunction "2_2") (pintype "passive"))
      (node (ref "IC1") (pin "9") (pinfunction "QH*_9") (pintype "tri_state"))
    )
    (net (code "42") (name "/RAIN1") (class "Default")
      (node (ref "R9") (pin "2") (pinfunction "2_2") (pintype "passive"))
      (node (ref "RAIN") (pin "1") (pinfunction "K1_1") (pintype "passive"))
    )
    (net (code "43") (name "/RAIN_GPIO") (class "Default")
      (node (ref "J1") (pin "8") (pinfunction "TXO_8") (pintype "output"))
      (node (ref "OK1") (pin "5") (pinfunction "COL_5") (pintype "passive"))
      (node (ref "R12") (pin "2") (pinfunction "2_2") (pintype "passive"))
    )
    (net (code "44") (name "/RELAY_GPIO") (class "Default")
      (node (ref "J1") (pin "10") (pinfunction "RXI_10") (pintype "input"))
      (node (ref "R32") (pin "2") (pinfunction "2_2") (pintype "passive"))
    )
    (net (code "45") (name "/SCL5V") (class "Default")
      (node (ref "I2C-5V-0") (pin "3") (pinfunction "3_3") (pintype "bidirectional"))
      (node (ref "I2C-5V-1") (pin "3") (pinfunction "3_3") (pintype "bidirectional"))
      (node (ref "I2C-5V-2") (pin "3") (pinfunction "3_3") (pintype "bidirectional"))
      (node (ref "I2C-5V-3") (pin "3") (pinfunction "3_3") (pintype "bidirectional"))
      (node (ref "IC2") (pin "6") (pinfunction "SCL_6") (pintype "bidirectional"))
      (node (ref "IC3") (pin "6") (pinfunction "SCL_6") (pintype "input"))
      (node (ref "IC4") (pin "6") (pinfunction "6_6") (pintype "input"))
      (node (ref "IC4B") (pin "6") (pinfunction "6_6") (pintype "bidirectional"))
      (node (ref "IC5") (pin "6") (pinfunction "6_6") (pintype "input"))
      (node (ref "IC5B") (pin "6") (pinfunction "6_6") (pintype "bidirectional"))
      (node (ref "Q2") (pin "D") (pinfunction "D_D") (pintype "passive"))
      (node (ref "R17") (pin "2") (pinfunction "2_2") (pintype "passive"))
    )
    (net (code "46") (name "/SCL_GPIO") (class "Default")
      (node (ref "J1") (pin "5") (pinfunction "SCL_5") (pintype "bidirectional"))
      (node (ref "Q2") (pin "S") (pinfunction "S_S") (pintype "passive"))
      (node (ref "R20") (pin "2") (pinfunction "2_2") (pintype "passive"))
    )
    (net (code "47") (name "/SDA5V") (class "Default")
      (node (ref "I2C-5V-0") (pin "2") (pinfunction "2_2") (pintype "bidirectional"))
      (node (ref "I2C-5V-1") (pin "2") (pinfunction "2_2") (pintype "bidirectional"))
      (node (ref "I2C-5V-2") (pin "2") (pinfunction "2_2") (pintype "bidirectional"))
      (node (ref "I2C-5V-3") (pin "2") (pinfunction "2_2") (pintype "bidirectional"))
      (node (ref "IC2") (pin "5") (pinfunction "SDA_5") (pintype "bidirectional"))
      (node (ref "IC3") (pin "5") (pinfunction "SDA_5") (pintype "bidirectional"))
      (node (ref "IC4") (pin "5") (pinfunction "5_5") (pintype "bidirectional"))
      (node (ref "IC4B") (pin "5") (pinfunction "5_5") (pintype "bidirectional"))
      (node (ref "IC5") (pin "5") (pinfunction "5_5") (pintype "bidirectional"))
      (node (ref "IC5B") (pin "5") (pinfunction "5_5") (pintype "bidirectional"))
      (node (ref "Q3") (pin "D") (pinfunction "D_D") (pintype "passive"))
      (node (ref "R18") (pin "2") (pinfunction "2_2") (pintype "passive"))
    )
    (net (code "48") (name "/SDA_GPIO") (class "Default")
      (node (ref "J1") (pin "3") (pinfunction "SDA_3") (pintype "bidirectional"))
      (node (ref "Q3") (pin "S") (pinfunction "S_S") (pintype "passive"))
      (node (ref "R19") (pin "2") (pinfunction "2_2") (pintype "passive"))
    )
    (net (code "49") (name "/TO_UPS_POWER_OFF_GPIO") (class "Default")
      (node (ref "J1") (pin "18") (pinfunction "GP24_18") (pintype "bidirectional"))
      (node (ref "R14") (pin "1") (pinfunction "1_1") (pintype "passive"))
    )
    (net (code "50") (name "/UPS1") (class "Default")
      (node (ref "OK3") (pin "4") (pinfunction "EMI_4") (pintype "passive"))
      (node (ref "UPS_DOWN") (pin "1") (pinfunction "K1_1") (pintype "passive"))
    )
    (net (code "51") (name "/UPS2") (class "Default")
      (node (ref "OK3") (pin "5") (pinfunction "COL_5") (pintype "passive"))
      (node (ref "UPS_DOWN") (pin "2") (pinfunction "K2_2") (pintype "passive"))
    )
    (net (code "52") (name "/WIND") (class "Default")
      (node (ref "R36") (pin "2") (pinfunction "2_2") (pintype "passive"))
      (node (ref "WIND") (pin "1") (pinfunction "K1_1") (pintype "passive"))
    )
    (net (code "53") (name "GND") (class "Default")
      (node (ref "C17") (pin "2") (pinfunction "2_2") (pintype "passive"))
      (node (ref "C18") (pin "C-") (pinfunction "C_EL-_C-") (pintype "passive"))
      (node (ref "C19") (pin "1") (pinfunction "1_1") (pintype "passive"))
      (node (ref "C2") (pin "C-") (pinfunction "C_EL-_C-") (pintype "passive"))
      (node (ref "C3") (pin "C-") (pinfunction "C_EL-_C-") (pintype "passive"))
      (node (ref "C4") (pin "C-") (pinfunction "C_EL-_C-") (pintype "passive"))
      (node (ref "C5") (pin "2") (pinfunction "2_2") (pintype "passive"))
      (node (ref "C6") (pin "2") (pinfunction "2_2") (pintype "passive"))
      (node (ref "C7") (pin "2") (pinfunction "2_2") (pintype "passive"))
      (node (ref "D2") (pin "A") (pinfunction "A_A") (pintype "passive"))
      (node (ref "D3") (pin "A") (pinfunction "A_A") (pintype "passive"))
      (node (ref "EXT_OUT") (pin "3") (pinfunction "3_3") (pintype "passive"))
      (node (ref "EXT_OUT") (pin "5") (pinfunction "5_5") (pintype "passive"))
      (node (ref "EXT_OUT") (pin "7") (pinfunction "7_7") (pintype "passive"))
      (node (ref "G1") (pin "-") (pinfunction "-_-") (pintype "passive"))
      (node (ref "I2C-5V-0") (pin "4") (pinfunction "4_4") (pintype "bidirectional"))
      (node (ref "I2C-5V-1") (pin "4") (pinfunction "4_4") (pintype "bidirectional"))
      (node (ref "I2C-5V-2") (pin "4") (pinfunction "4_4") (pintype "bidirectional"))
      (node (ref "I2C-5V-3") (pin "4") (pinfunction "4_4") (pintype "bidirectional"))
      (node (ref "IC2") (pin "4") (pinfunction "GND_4") (pintype "power_in"))
      (node (ref "IC3") (pin "3") (pinfunction "A0_3") (pintype "input"))
      (node (ref "IC3") (pin "4") (pinfunction "VSS_4") (pintype "power_in"))
      (node (ref "IC4") (pin "3") (pinfunction "3_3") (pintype "input"))
      (node (ref "IC4") (pin "4") (pinfunction "4_4") (pintype "power_in"))
      (node (ref "IC4B") (pin "3") (pinfunction "3_3") (pintype "bidirectional"))
      (node (ref "IC4B") (pin "4") (pinfunction "4_4") (pintype "bidirectional"))
      (node (ref "IC5") (pin "4") (pinfunction "4_4") (pintype "power_in"))
      (node (ref "IC5B") (pin "4") (pinfunction "4_4") (pintype "bidirectional"))
      (node (ref "J1") (pin "14") (pinfunction "GND_14") (pintype "power_in"))
      (node (ref "J1") (pin "20") (pinfunction "GND_20") (pintype "power_in"))
      (node (ref "J1") (pin "25") (pinfunction "GND_25") (pintype "power_in"))
      (node (ref "J1") (pin "30") (pinfunction "GND_30") (pintype "power_in"))
      (node (ref "J1") (pin "34") (pinfunction "GND_34") (pintype "power_in"))
      (node (ref "J1") (pin "39") (pinfunction "GND_39") (pintype "power_in"))
      (node (ref "J1") (pin "6") (pinfunction "GND_6") (pintype "power_in"))
      (node (ref "J1") (pin "9") (pinfunction "GND_9") (pintype "power_in"))
      (node (ref "K9") (pin "2") (pinfunction "2_2") (pintype "passive"))
      (node (ref "LED13") (pin "K") (pinfunction "C_K") (pintype "passive"))
      (node (ref "OK1") (pin "2") (pinfunction "C_2") (pintype "passive"))
      (node (ref "OK1") (pin "4") (pinfunction "EMI_4") (pintype "passive"))
      (node (ref "OK2") (pin "2") (pinfunction "C_2") (pintype "passive"))
      (node (ref "OK2") (pin "4") (pinfunction "EMI_4") (pintype "passive"))
      (node (ref "OK3") (pin "2") (pinfunction "C_2") (pintype "passive"))
      (node (ref "OK4") (pin "4") (pinfunction "EMI_4") (pintype "passive"))
      (node (ref "OK5") (pin "2") (pinfunction "C_2") (pintype "passive"))
      (node (ref "OK5") (pin "4") (pinfunction "EMI_4") (pintype "passive"))
      (node (ref "OK6") (pin "2") (pinfunction "C_2") (pintype "passive"))
      (node (ref "OK6") (pin "4") (pinfunction "EMI_4") (pintype "passive"))
      (node (ref "POW5V") (pin "2") (pinfunction "K2_2") (pintype "passive"))
      (node (ref "U1") (pin "GND") (pinfunction "GND_GND") (pintype "power_in"))
      (node (ref "ULN1") (pin "9") (pinfunction "9_9") (pintype "bidirectional"))
    )
    (net (code "54") (name "Net-(C1-Pad1)") (class "Default")
      (node (ref "C1") (pin "1") (pinfunction "1_1") (pintype "passive"))
      (node (ref "R21") (pin "2") (pinfunction "2_2") (pintype "passive"))
    )
    (net (code "55") (name "Net-(C1-Pad2)") (class "Default")
      (node (ref "C1") (pin "2") (pinfunction "2_2") (pintype "passive"))
      (node (ref "D1") (pin "C") (pinfunction "C_C") (pintype "passive"))
      (node (ref "R15") (pin "2") (pinfunction "2_2") (pintype "passive"))
    )
    (net (code "56") (name "Net-(C8-Pad2)") (class "Default")
      (node (ref "C8") (pin "2") (pinfunction "2_2") (pintype "passive"))
      (node (ref "R22") (pin "1") (pinfunction "1_1") (pintype "passive"))
    )
    (net (code "57") (name "Net-(C9-Pad2)") (class "Default")
      (node (ref "C9") (pin "2") (pinfunction "2_2") (pintype "passive"))
      (node (ref "R23") (pin "1") (pinfunction "1_1") (pintype "passive"))
    )
    (net (code "58") (name "Net-(C10-Pad2)") (class "Default")
      (node (ref "C10") (pin "2") (pinfunction "2_2") (pintype "passive"))
      (node (ref "R24") (pin "1") (pinfunction "1_1") (pintype "passive"))
    )
    (net (code "59") (name "Net-(C11-Pad2)") (class "Default")
      (node (ref "C11") (pin "2") (pinfunction "2_2") (pintype "passive"))
      (node (ref "R25") (pin "1") (pinfunction "1_1") (pintype "passive"))
    )
    (net (code "60") (name "Net-(C12-Pad2)") (class "Default")
      (node (ref "C12") (pin "2") (pinfunction "2_2") (pintype "passive"))
      (node (ref "R26") (pin "1") (pinfunction "1_1") (pintype "passive"))
    )
    (net (code "61") (name "Net-(C13-Pad2)") (class "Default")
      (node (ref "C13") (pin "2") (pinfunction "2_2") (pintype "passive"))
      (node (ref "R27") (pin "1") (pinfunction "1_1") (pintype "passive"))
    )
    (net (code "62") (name "Net-(C14-Pad2)") (class "Default")
      (node (ref "C14") (pin "2") (pinfunction "2_2") (pintype "passive"))
      (node (ref "R28") (pin "1") (pinfunction "1_1") (pintype "passive"))
    )
    (net (code "63") (name "Net-(C15-Pad2)") (class "Default")
      (node (ref "C15") (pin "2") (pinfunction "2_2") (pintype "passive"))
      (node (ref "R29") (pin "1") (pinfunction "1_1") (pintype "passive"))
    )
    (net (code "64") (name "Net-(C16-Pad2)") (class "Default")
      (node (ref "C16") (pin "2") (pinfunction "2_2") (pintype "passive"))
      (node (ref "R31") (pin "1") (pinfunction "1_1") (pintype "passive"))
    )
    (net (code "65") (name "Net-(IC1A-RCK)") (class "Default")
      (node (ref "C19") (pin "2") (pinfunction "2_2") (pintype "passive"))
      (node (ref "IC1") (pin "12") (pinfunction "RCK_12") (pintype "input"))
      (node (ref "R38") (pin "2") (pinfunction "2_2") (pintype "passive"))
      (node (ref "R39") (pin "2") (pinfunction "2_2") (pintype "passive"))
    )
    (net (code "66") (name "Net-(LED1-PadA)") (class "Default")
      (node (ref "LED1") (pin "A") (pinfunction "A_A") (pintype "passive"))
      (node (ref "R1") (pin "1") (pinfunction "1_1") (pintype "passive"))
    )
    (net (code "67") (name "Net-(LED2-PadA)") (class "Default")
      (node (ref "LED2") (pin "A") (pinfunction "A_A") (pintype "passive"))
      (node (ref "R2") (pin "1") (pinfunction "1_1") (pintype "passive"))
    )
    (net (code "68") (name "Net-(LED3-PadA)") (class "Default")
      (node (ref "LED3") (pin "A") (pinfunction "A_A") (pintype "passive"))
      (node (ref "R3") (pin "1") (pinfunction "1_1") (pintype "passive"))
    )
    (net (code "69") (name "Net-(LED4-PadA)") (class "Default")
      (node (ref "LED4") (pin "A") (pinfunction "A_A") (pintype "passive"))
      (node (ref "R4") (pin "1") (pinfunction "1_1") (pintype "passive"))
    )
    (net (code "70") (name "Net-(LED5-PadA)") (class "Default")
      (node (ref "LED5") (pin "A") (pinfunction "A_A") (pintype "passive"))
      (node (ref "R5") (pin "1") (pinfunction "1_1") (pintype "passive"))
    )
    (net (code "71") (name "Net-(LED6-PadA)") (class "Default")
      (node (ref "LED6") (pin "A") (pinfunction "A_A") (pintype "passive"))
      (node (ref "R6") (pin "1") (pinfunction "1_1") (pintype "passive"))
    )
    (net (code "72") (name "Net-(LED7-PadA)") (class "Default")
      (node (ref "LED7") (pin "A") (pinfunction "A_A") (pintype "passive"))
      (node (ref "R7") (pin "1") (pinfunction "1_1") (pintype "passive"))
    )
    (net (code "73") (name "Net-(LED8-PadA)") (class "Default")
      (node (ref "LED8") (pin "A") (pinfunction "A_A") (pintype "passive"))
      (node (ref "R8") (pin "1") (pinfunction "1_1") (pintype "passive"))
    )
    (net (code "74") (name "Net-(LED9-C)") (class "Default")
      (node (ref "LED9") (pin "K") (pinfunction "C_K") (pintype "passive"))
      (node (ref "OK1") (pin "1") (pinfunction "A_1") (pintype "passive"))
    )
    (net (code "75") (name "Net-(LED9-PadA)") (class "Default")
      (node (ref "LED9") (pin "A") (pinfunction "A_A") (pintype "passive"))
      (node (ref "R9") (pin "1") (pinfunction "1_1") (pintype "passive"))
    )
    (net (code "76") (name "Net-(LED10-C)") (class "Default")
      (node (ref "LED10") (pin "K") (pinfunction "C_K") (pintype "passive"))
      (node (ref "OK2") (pin "1") (pinfunction "A_1") (pintype "passive"))
    )
    (net (code "77") (name "Net-(LED10-PadA)") (class "Default")
      (node (ref "LED10") (pin "A") (pinfunction "A_A") (pintype "passive"))
      (node (ref "R10") (pin "1") (pinfunction "1_1") (pintype "passive"))
    )
    (net (code "78") (name "Net-(LED11-C)") (class "Default")
      (node (ref "LED11") (pin "K") (pinfunction "C_K") (pintype "passive"))
      (node (ref "OK3") (pin "1") (pinfunction "A_1") (pintype "passive"))
    )
    (net (code "79") (name "Net-(LED11-PadA)") (class "Default")
      (node (ref "LED11") (pin "A") (pinfunction "A_A") (pintype "passive"))
      (node (ref "R14") (pin "2") (pinfunction "2_2") (pintype "passive"))
    )
    (net (code "80") (name "Net-(LED12-C)") (class "Default")
      (node (ref "LED12") (pin "K") (pinfunction "C_K") (pintype "passive"))
      (node (ref "OK4") (pin "1") (pinfunction "A_1") (pintype "passive"))
    )
    (net (code "81") (name "Net-(LED12-PadA)") (class "Default")
      (node (ref "LED12") (pin "A") (pinfunction "A_A") (pintype "passive"))
      (node (ref "R15") (pin "1") (pinfunction "1_1") (pintype "passive"))
    )
    (net (code "82") (name "Net-(LED13-PadA)") (class "Default")
      (node (ref "LED13") (pin "A") (pinfunction "A_A") (pintype "passive"))
      (node (ref "R30") (pin "1") (pinfunction "1_1") (pintype "passive"))
    )
    (net (code "83") (name "Net-(LED14-C)") (class "Default")
      (node (ref "LED14") (pin "K") (pinfunction "C_K") (pintype "passive"))
      (node (ref "OK6") (pin "1") (pinfunction "A_1") (pintype "passive"))
    )
    (net (code "84") (name "Net-(LED14-PadA)") (class "Default")
      (node (ref "LED14") (pin "A") (pinfunction "A_A") (pintype "passive"))
      (node (ref "R36") (pin "1") (pinfunction "1_1") (pintype "passive"))
    )
    (net (code "85") (name "Net-(OK5-A)") (class "Default")
      (node (ref "OK5") (pin "1") (pinfunction "A_1") (pintype "passive"))
      (node (ref "R32") (pin "1") (pinfunction "1_1") (pintype "passive"))
    )
    (net (code "86") (name "Net-(OK5-COL)") (class "Default")
      (node (ref "OK5") (pin "5") (pinfunction "COL_5") (pintype "passive"))
      (node (ref "R33") (pin "2") (pinfunction "2_2") (pintype "passive"))
      (node (ref "R34") (pin "2") (pinfunction "2_2") (pintype "passive"))
    )
    (net (code "87") (name "Net-(Q4-B)") (class "Default")
      (node (ref "Q4") (pin "2") (pinfunction "B_2") (pintype "passive"))
      (node (ref "R33") (pin "1") (pinfunction "1_1") (pintype "passive"))
    )
    (net (code "88") (name "Net-(Q4-C)") (class "Default")
      (node (ref "D3") (pin "C") (pinfunction "C_C") (pintype "passive"))
      (node (ref "K9") (pin "1") (pinfunction "1_1") (pintype "passive"))
      (node (ref "Q4") (pin "3") (pinfunction "C_3") (pintype "passive"))
      (node (ref "R30") (pin "2") (pinfunction "2_2") (pintype "passive"))
    )
    (net (code "89") (name "VCC") (class "Default")
      (node (ref "C17") (pin "1") (pinfunction "1_1") (pintype "passive"))
      (node (ref "C18") (pin "C+") (pinfunction "C_EL+_C+") (pintype "passive"))
      (node (ref "C3") (pin "C+") (pinfunction "C_EL+_C+") (pintype "passive"))
      (node (ref "C6") (pin "1") (pinfunction "1_1") (pintype "passive"))
      (node (ref "D2") (pin "C") (pinfunction "C_C") (pintype "passive"))
      (node (ref "EXT_OUT") (pin "1") (pinfunction "1_1") (pintype "passive"))
      (node (ref "I2C-5V-0") (pin "1") (pinfunction "1_1") (pintype "bidirectional"))
      (node (ref "I2C-5V-1") (pin "1") (pinfunction "1_1") (pintype "bidirectional"))
      (node (ref "I2C-5V-2") (pin "1") (pinfunction "1_1") (pintype "bidirectional"))
      (node (ref "I2C-5V-3") (pin "1") (pinfunction "1_1") (pintype "bidirectional"))
      (node (ref "IC1") (pin "10") (pinfunction "SCL_10") (pintype "input"))
      (node (ref "IC2") (pin "8") (pinfunction "VCC_8") (pintype "power_in"))
      (node (ref "IC3") (pin "8") (pinfunction "VDD_8") (pintype "power_in"))
      (node (ref "IC4") (pin "8") (pinfunction "8_8") (pintype "power_in"))
      (node (ref "IC4B") (pin "8") (pinfunction "8_8") (pintype "bidirectional"))
      (node (ref "IC5") (pin "8") (pinfunction "8_8") (pintype "power_in"))
      (node (ref "IC5B") (pin "8") (pinfunction "8_8") (pintype "bidirectional"))
      (node (ref "J1") (pin "2") (pinfunction "5V_2") (pintype "power_in"))
      (node (ref "J1") (pin "4") (pinfunction "5V_4") (pintype "power_in"))
      (node (ref "K1") (pin "1") (pinfunction "1_1") (pintype "passive"))
      (node (ref "K2") (pin "1") (pinfunction "1_1") (pintype "passive"))
      (node (ref "K3") (pin "1") (pinfunction "1_1") (pintype "passive"))
      (node (ref "K4") (pin "1") (pinfunction "1_1") (pintype "passive"))
      (node (ref "K5") (pin "1") (pinfunction "1_1") (pintype "passive"))
      (node (ref "K6") (pin "1") (pinfunction "1_1") (pintype "passive"))
      (node (ref "K7") (pin "1") (pinfunction "1_1") (pintype "passive"))
      (node (ref "K8") (pin "1") (pinfunction "1_1") (pintype "passive"))
      (node (ref "POW5V") (pin "1") (pinfunction "K1_1") (pintype "passive"))
      (node (ref "PRESSURE") (pin "2") (pinfunction "K2_2") (pintype "passive"))
      (node (ref "Q4") (pin "1") (pinfunction "E_1") (pintype "passive"))
      (node (ref "R1") (pin "2") (pinfunction "2_2") (pintype "passive"))
      (node (ref "R11") (pin "1") (pinfunction "1_1") (pintype "passive"))
      (node (ref "R17") (pin "1") (pinfunction "1_1") (pintype "passive"))
      (node (ref "R18") (pin "1") (pinfunction "1_1") (pintype "passive"))
      (node (ref "R2") (pin "2") (pinfunction "2_2") (pintype "passive"))
      (node (ref "R3") (pin "2") (pinfunction "2_2") (pintype "passive"))
      (node (ref "R34") (pin "1") (pinfunction "1_1") (pintype "passive"))
      (node (ref "R35") (pin "1") (pinfunction "1_1") (pintype "passive"))
      (node (ref "R39") (pin "1") (pinfunction "1_1") (pintype "passive"))
      (node (ref "R4") (pin "2") (pinfunction "2_2") (pintype "passive"))
      (node (ref "R5") (pin "2") (pinfunction "2_2") (pintype "passive"))
      (node (ref "R6") (pin "2") (pinfunction "2_2") (pintype "passive"))
      (node (ref "R7") (pin "2") (pinfunction "2_2") (pintype "passive"))
      (node (ref "R8") (pin "2") (pinfunction "2_2") (pintype "passive"))
      (node (ref "RAIN") (pin "2") (pinfunction "K2_2") (pintype "passive"))
      (node (ref "ULN1") (pin "10") (pinfunction "10_10") (pintype "bidirectional"))
      (node (ref "WIND") (pin "2") (pinfunction "K2_2") (pintype "passive"))
    )
    (net (code "90") (name "unconnected-(G1-+-Pad+@1)") (class "Default")
      (node (ref "G1") (pin "+@1") (pinfunction "+_+@1") (pintype "passive"))
    )
    (net (code "91") (name "unconnected-(G1-+-Pad+@2)") (class "Default")
      (node (ref "G1") (pin "+@2") (pinfunction "+_+@2") (pintype "passive"))
    )
    (net (code "92") (name "unconnected-(G1-+-Pad+@3)") (class "Default")
      (node (ref "G1") (pin "+@3") (pinfunction "+_+@3") (pintype "passive"))
    )
    (net (code "93") (name "unconnected-(G1-+-Pad+@4)") (class "Default")
      (node (ref "G1") (pin "+@4") (pinfunction "+_+@4") (pintype "passive"))
    )
    (net (code "94") (name "unconnected-(G1---Pad-@1)") (class "Default")
      (node (ref "G1") (pin "-@1") (pinfunction "-_-@1") (pintype "passive"))
    )
    (net (code "95") (name "unconnected-(IC2-SQW{slash}OUT-Pad7)") (class "Default")
      (node (ref "IC2") (pin "7") (pinfunction "SQW/OUT_7") (pintype "bidirectional"))
    )
    (net (code "96") (name "unconnected-(IC3-OSCO-Pad2)") (class "Default")
      (node (ref "IC3") (pin "2") (pinfunction "OSCO_2") (pintype "output"))
    )
    (net (code "97") (name "unconnected-(IC3-~{INT}-Pad7)") (class "Default")
      (node (ref "IC3") (pin "7") (pinfunction "~{INT}_7") (pintype "open_collector"))
    )
    (net (code "98") (name "unconnected-(IC4-Pad2)") (class "Default")
      (node (ref "IC4") (pin "2") (pinfunction "2_2") (pintype "output"))
    )
    (net (code "99") (name "unconnected-(IC4-Pad7)") (class "Default")
      (node (ref "IC4") (pin "7") (pinfunction "7_7") (pintype "open_collector"))
    )
    (net (code "100") (name "unconnected-(IC4B-Pad2)") (class "Default")
      (node (ref "IC4B") (pin "2") (pinfunction "2_2") (pintype "bidirectional"))
    )
    (net (code "101") (name "unconnected-(IC4B-Pad7)") (class "Default")
      (node (ref "IC4B") (pin "7") (pinfunction "7_7") (pintype "bidirectional"))
    )
    (net (code "102") (name "unconnected-(IC5-Pad7)") (class "Default")
      (node (ref "IC5") (pin "7") (pinfunction "7_7") (pintype "open_collector"))
    )
    (net (code "103") (name "unconnected-(IC5B-Pad7)") (class "Default")
      (node (ref "IC5B") (pin "7") (pinfunction "7_7") (pintype "bidirectional"))
    )
    (net (code "104") (name "unconnected-(J1-CE0-Pad24)") (class "Default")
      (node (ref "J1") (pin "24") (pinfunction "CE0_24") (pintype "output"))
    )
    (net (code "105") (name "unconnected-(J1-CE1-Pad26)") (class "Default")
      (node (ref "J1") (pin "26") (pinfunction "CE1_26") (pintype "output"))
    )
    (net (code "106") (name "unconnected-(J1-GP5-Pad29)") (class "Default")
      (node (ref "J1") (pin "29") (pinfunction "GP5_29") (pintype "bidirectional"))
    )
    (net (code "107") (name "unconnected-(J1-GP6-Pad31)") (class "Default")
      (node (ref "J1") (pin "31") (pinfunction "GP6_31") (pintype "bidirectional"))
    )
    (net (code "108") (name "unconnected-(J1-GP12-Pad32)") (class "Default")
      (node (ref "J1") (pin "32") (pinfunction "GP12_32") (pintype "bidirectional"))
    )
    (net (code "109") (name "unconnected-(J1-GP13-Pad33)") (class "Default")
      (node (ref "J1") (pin "33") (pinfunction "GP13_33") (pintype "bidirectional"))
    )
    (net (code "110") (name "unconnected-(J1-GP16-Pad36)") (class "Default")
      (node (ref "J1") (pin "36") (pinfunction "GP16_36") (pintype "bidirectional"))
    )
    (net (code "111") (name "unconnected-(J1-GP19-Pad35)") (class "Default")
      (node (ref "J1") (pin "35") (pinfunction "GP19_35") (pintype "bidirectional"))
    )
    (net (code "112") (name "unconnected-(J1-GP20-Pad38)") (class "Default")
      (node (ref "J1") (pin "38") (pinfunction "GP20_38") (pintype "bidirectional"))
    )
    (net (code "113") (name "unconnected-(J1-GP21-Pad40)") (class "Default")
      (node (ref "J1") (pin "40") (pinfunction "GP21_40") (pintype "bidirectional"))
    )
    (net (code "114") (name "unconnected-(J1-GP25-Pad22)") (class "Default")
      (node (ref "J1") (pin "22") (pinfunction "GP25_22") (pintype "bidirectional"))
    )
    (net (code "115") (name "unconnected-(J1-GP26-Pad37)") (class "Default")
      (node (ref "J1") (pin "37") (pinfunction "GP26_37") (pintype "bidirectional"))
    )
    (net (code "116") (name "unconnected-(J1-ID_SC-Pad28)") (class "Default")
      (node (ref "J1") (pin "28") (pinfunction "ID_SC_28") (pintype "bidirectional"))
    )
    (net (code "117") (name "unconnected-(J1-ID_SD-Pad27)") (class "Default")
      (node (ref "J1") (pin "27") (pinfunction "ID_SD_27") (pintype "bidirectional"))
    )
    (net (code "118") (name "unconnected-(J1-MISO-Pad21)") (class "Default")
      (node (ref "J1") (pin "21") (pinfunction "MISO_21") (pintype "input"))
    )
    (net (code "119") (name "unconnected-(J1-SCLK-Pad23)") (class "Default")
      (node (ref "J1") (pin "23") (pinfunction "SCLK_23") (pintype "output"))
    )
    (net (code "120") (name "unconnected-(K1B-O-PadO1)") (class "Default")
      (node (ref "K1") (pin "O1") (pinfunction "O_O1") (pintype "passive"))
    )
    (net (code "121") (name "unconnected-(K1C-O-PadO2)") (class "Default")
      (node (ref "K1") (pin "O2") (pinfunction "O_O2") (pintype "passive"))
    )
    (net (code "122") (name "unconnected-(K2B-O-PadO1)") (class "Default")
      (node (ref "K2") (pin "O1") (pinfunction "O_O1") (pintype "passive"))
    )
    (net (code "123") (name "unconnected-(K2C-O-PadO2)") (class "Default")
      (node (ref "K2") (pin "O2") (pinfunction "O_O2") (pintype "passive"))
    )
    (net (code "124") (name "unconnected-(K3B-O-PadO1)") (class "Default")
      (node (ref "K3") (pin "O1") (pinfunction "O_O1") (pintype "passive"))
    )
    (net (code "125") (name "unconnected-(K3C-O-PadO2)") (class "Default")
      (node (ref "K3") (pin "O2") (pinfunction "O_O2") (pintype "passive"))
    )
    (net (code "126") (name "unconnected-(K4B-O-PadO1)") (class "Default")
      (node (ref "K4") (pin "O1") (pinfunction "O_O1") (pintype "passive"))
    )
    (net (code "127") (name "unconnected-(K4C-O-PadO2)") (class "Default")
      (node (ref "K4") (pin "O2") (pinfunction "O_O2") (pintype "passive"))
    )
    (net (code "128") (name "unconnected-(K5B-O-PadO1)") (class "Default")
      (node (ref "K5") (pin "O1") (pinfunction "O_O1") (pintype "passive"))
    )
    (net (code "129") (name "unconnected-(K5C-O-PadO2)") (class "Default")
      (node (ref "K5") (pin "O2") (pinfunction "O_O2") (pintype "passive"))
    )
    (net (code "130") (name "unconnected-(K6B-O-PadO1)") (class "Default")
      (node (ref "K6") (pin "O1") (pinfunction "O_O1") (pintype "passive"))
    )
    (net (code "131") (name "unconnected-(K6C-O-PadO2)") (class "Default")
      (node (ref "K6") (pin "O2") (pinfunction "O_O2") (pintype "passive"))
    )
    (net (code "132") (name "unconnected-(K7B-O-PadO1)") (class "Default")
      (node (ref "K7") (pin "O1") (pinfunction "O_O1") (pintype "passive"))
    )
    (net (code "133") (name "unconnected-(K7C-O-PadO2)") (class "Default")
      (node (ref "K7") (pin "O2") (pinfunction "O_O2") (pintype "passive"))
    )
    (net (code "134") (name "unconnected-(K8B-O-PadO1)") (class "Default")
      (node (ref "K8") (pin "O1") (pinfunction "O_O1") (pintype "passive"))
    )
    (net (code "135") (name "unconnected-(K8C-O-PadO2)") (class "Default")
      (node (ref "K8") (pin "O2") (pinfunction "O_O2") (pintype "passive"))
    )
    (net (code "136") (name "unconnected-(K9B-O-PadO1)") (class "Default")
      (node (ref "K9") (pin "O1") (pinfunction "O_O1") (pintype "passive"))
    )
    (net (code "137") (name "unconnected-(K9C-O-PadO2)") (class "Default")
      (node (ref "K9") (pin "O2") (pinfunction "O_O2") (pintype "passive"))
    )
    (net (code "138") (name "unconnected-(OK1-BAS-Pad6)") (class "Default")
      (node (ref "OK1") (pin "6") (pinfunction "BAS_6") (pintype "passive"))
    )
    (net (code "139") (name "unconnected-(OK2-BAS-Pad6)") (class "Default")
      (node (ref "OK2") (pin "6") (pinfunction "BAS_6") (pintype "passive"))
    )
    (net (code "140") (name "unconnected-(OK3-BAS-Pad6)") (class "Default")
      (node (ref "OK3") (pin "6") (pinfunction "BAS_6") (pintype "passive"))
    )
    (net (code "141") (name "unconnected-(OK4-BAS-Pad6)") (class "Default")
      (node (ref "OK4") (pin "6") (pinfunction "BAS_6") (pintype "passive"))
    )
    (net (code "142") (name "unconnected-(OK5-BAS-Pad6)") (class "Default")
      (node (ref "OK5") (pin "6") (pinfunction "BAS_6") (pintype "passive"))
    )
    (net (code "143") (name "unconnected-(OK6-BAS-Pad6)") (class "Default")
      (node (ref "OK6") (pin "6") (pinfunction "BAS_6") (pintype "passive"))
    )
    (net (code "144") (name "unconnected-(U1-PadNULL)") (class "Default")
      (node (ref "U1") (pin "NULL") (pinfunction "NULL_NULL") (pintype "no_connect"))
    )
  )
)
